# FILTER.net
KiCad netlist of a schematic drawn in Altium Designer
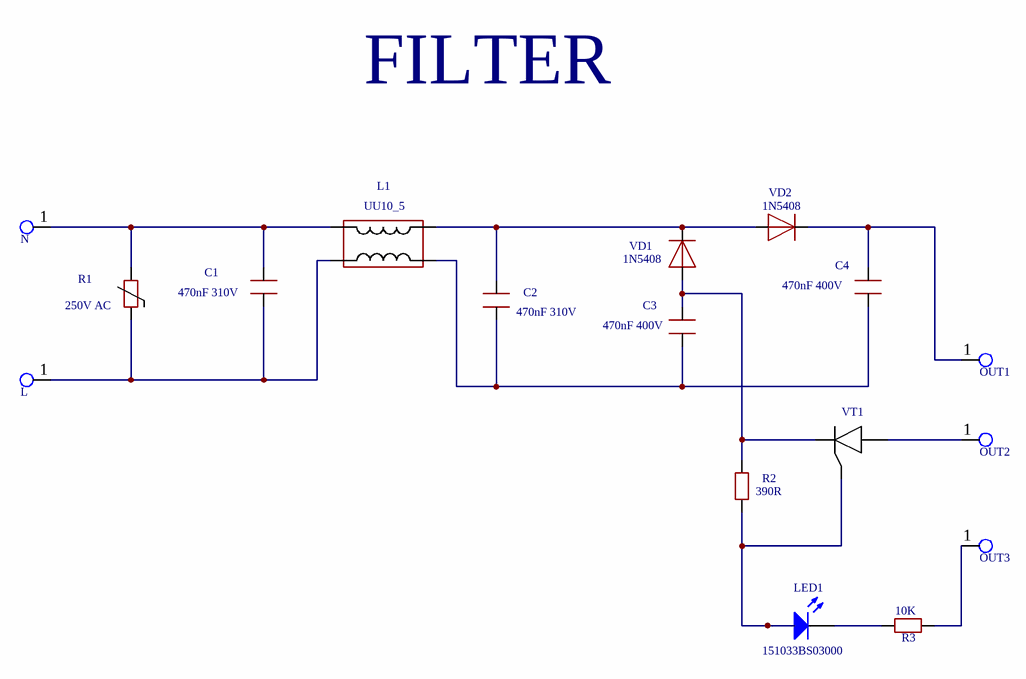
[diagram p0: FILTER.SchDoc]

(export (version "E")
  (design (tool "Eeschema 10.0.6"))
  (components
    (comp (ref "C1")
      (value "470nF 310V")
      (footprint "CAP_FILM")
      (libsource (lib "CAP_FILM") (part "CAP_FILM"))
    )
    (comp (ref "C2")
      (value "470nF 310V")
      (footprint "CAP_FILM")
      (libsource (lib "CAP_FILM") (part "CAP_FILM"))
    )
    (comp (ref "C3")
      (value "470nF 400V")
      (footprint "CAP 225J 400V")
      (libsource (lib "CAP 225J 400V") (part "CAP 225J 400V"))
    )
    (comp (ref "C4")
      (value "470nF 400V")
      (footprint "CAP 225J 400V")
      (libsource (lib "CAP 225J 400V") (part "CAP 225J 400V"))
    )
    (comp (ref "L")
      (value "Test_Point_PCB")
      (footprint "Test_Point")
      (description "Test_Point")
      (libsource (lib "TEST_POINT") (part "TP_PCB?"))
    )
    (comp (ref "L1") (value "UU10_5") (footprint "UU10_5") (libsource (lib "UU10_5") (part "UU10_5")))
    (comp (ref "LED1")
      (value "151033BS03000")
      (footprint "Type 3mm")
      (description "THT LED round mono-color waterclear, WL-TMRW , Blue")
      (fields (field (name "MANUFACTURER") "Wuerth Elektronik"))
      (libsource (lib "Optic-LED") (part "151033BS03000"))
    )
    (comp (ref "N")
      (value "Test_Point_PCB")
      (footprint "Test_Point")
      (description "Test_Point")
      (libsource (lib "") (part "TP_PCB?_1"))
    )
    (comp (ref "OUT1")
      (value "Test_Point_PCB")
      (footprint "Test_Point")
      (description "Test_Point")
      (libsource (lib "TEST_POINT") (part "TP_PCB?"))
    )
    (comp (ref "OUT2")
      (value "Test_Point_PCB")
      (footprint "Test_Point")
      (description "Test_Point")
      (libsource (lib "TEST_POINT") (part "TP_PCB?"))
    )
    (comp (ref "OUT3")
      (value "Test_Point_PCB")
      (footprint "Test_Point")
      (description "Test_Point")
      (libsource (lib "TEST_POINT") (part "TP_PCB?"))
    )
    (comp (ref "R1") (value "250V AC") (footprint "VARISTOR") (libsource (lib "RES") (part "VARISTOR")))
    (comp (ref "R2") (value "390R") (footprint "RES025W") (libsource (lib "RES") (part "RES")))
    (comp (ref "R3") (value "10K") (footprint "RES025W") (libsource (lib "RES") (part "RES")))
    (comp (ref "VD1") (value "1N5408") (footprint "1N5408") (libsource (lib "1N5408") (part "DIODE")))
    (comp (ref "VD2") (value "1N5408") (footprint "1N5408") (libsource (lib "1N5408") (part "DIODE")))
    (comp (ref "VT1") (value "TYN412") (footprint "TO-220-3") (libsource (lib "TYN412") (part "TYN412")))
  )
  (nets
    (net (code "1") (name "Net-(C1-A)") (class "Default")
      (node (ref "C1") (pin "2") (pinfunction "A_2") (pintype "passive"))
      (node (ref "L1") (pin "1") (pintype "passive"))
      (node (ref "N") (pin "1") (pinfunction "G9_1") (pintype "passive"))
      (node (ref "R1") (pin "2") (pintype "passive"))
    )
    (net (code "2") (name "Net-(C1-C)") (class "Default")
      (node (ref "C1") (pin "1") (pinfunction "C_1") (pintype "passive"))
      (node (ref "L") (pin "1") (pinfunction "G9_1") (pintype "passive"))
      (node (ref "L1") (pin "2") (pintype "passive"))
      (node (ref "R1") (pin "1") (pintype "passive"))
    )
    (net (code "3") (name "Net-(C2-A)") (class "Default")
      (node (ref "C2") (pin "2") (pinfunction "A_2") (pintype "passive"))
      (node (ref "L1") (pin "4") (pintype "passive"))
      (node (ref "VD1") (pin "1") (pinfunction "C_1") (pintype "passive"))
      (node (ref "VD2") (pin "2") (pinfunction "A_2") (pintype "passive"))
    )
    (net (code "4") (name "Net-(C2-C)") (class "Default")
      (node (ref "C2") (pin "1") (pinfunction "C_1") (pintype "passive"))
      (node (ref "C3") (pin "2") (pinfunction "A_2") (pintype "passive"))
      (node (ref "C4") (pin "2") (pinfunction "A_2") (pintype "passive"))
      (node (ref "L1") (pin "3") (pintype "passive"))
    )
    (net (code "5") (name "Net-(C3-C)") (class "Default")
      (node (ref "C3") (pin "1") (pinfunction "C_1") (pintype "passive"))
      (node (ref "R2") (pin "2") (pintype "passive"))
      (node (ref "VD1") (pin "2") (pinfunction "A_2") (pintype "passive"))
      (node (ref "VT1") (pin "1") (pintype "passive"))
    )
    (net (code "6") (name "Net-(C4-C)") (class "Default")
      (node (ref "C4") (pin "1") (pinfunction "C_1") (pintype "passive"))
      (node (ref "OUT1") (pin "1") (pinfunction "G9_1") (pintype "passive"))
      (node (ref "VD2") (pin "1") (pinfunction "C_1") (pintype "passive"))
    )
    (net (code "7") (name "Net-(LED1-A)") (class "Default")
      (node (ref "LED1") (pin "2") (pinfunction "A_2") (pintype "passive"))
      (node (ref "R2") (pin "1") (pintype "passive"))
      (node (ref "VT1") (pin "3") (pintype "passive"))
    )
    (net (code "8") (name "Net-(LED1-K)") (class "Default")
      (node (ref "LED1") (pin "1") (pinfunction "K_1") (pintype "passive"))
      (node (ref "R3") (pin "1") (pintype "passive"))
    )
    (net (code "9") (name "Net-(OUT2-G9)") (class "Default")
      (node (ref "OUT2") (pin "1") (pinfunction "G9_1") (pintype "passive"))
      (node (ref "VT1") (pin "2") (pintype "passive"))
    )
    (net (code "10") (name "Net-(OUT3-G9)") (class "Default")
      (node (ref "OUT3") (pin "1") (pinfunction "G9_1") (pintype "passive"))
      (node (ref "R3") (pin "2") (pintype "passive"))
    )
  )
)
